# Zio_Qwiic_Hub.net
KiCad netlist of a schematic drawn in EAGLE
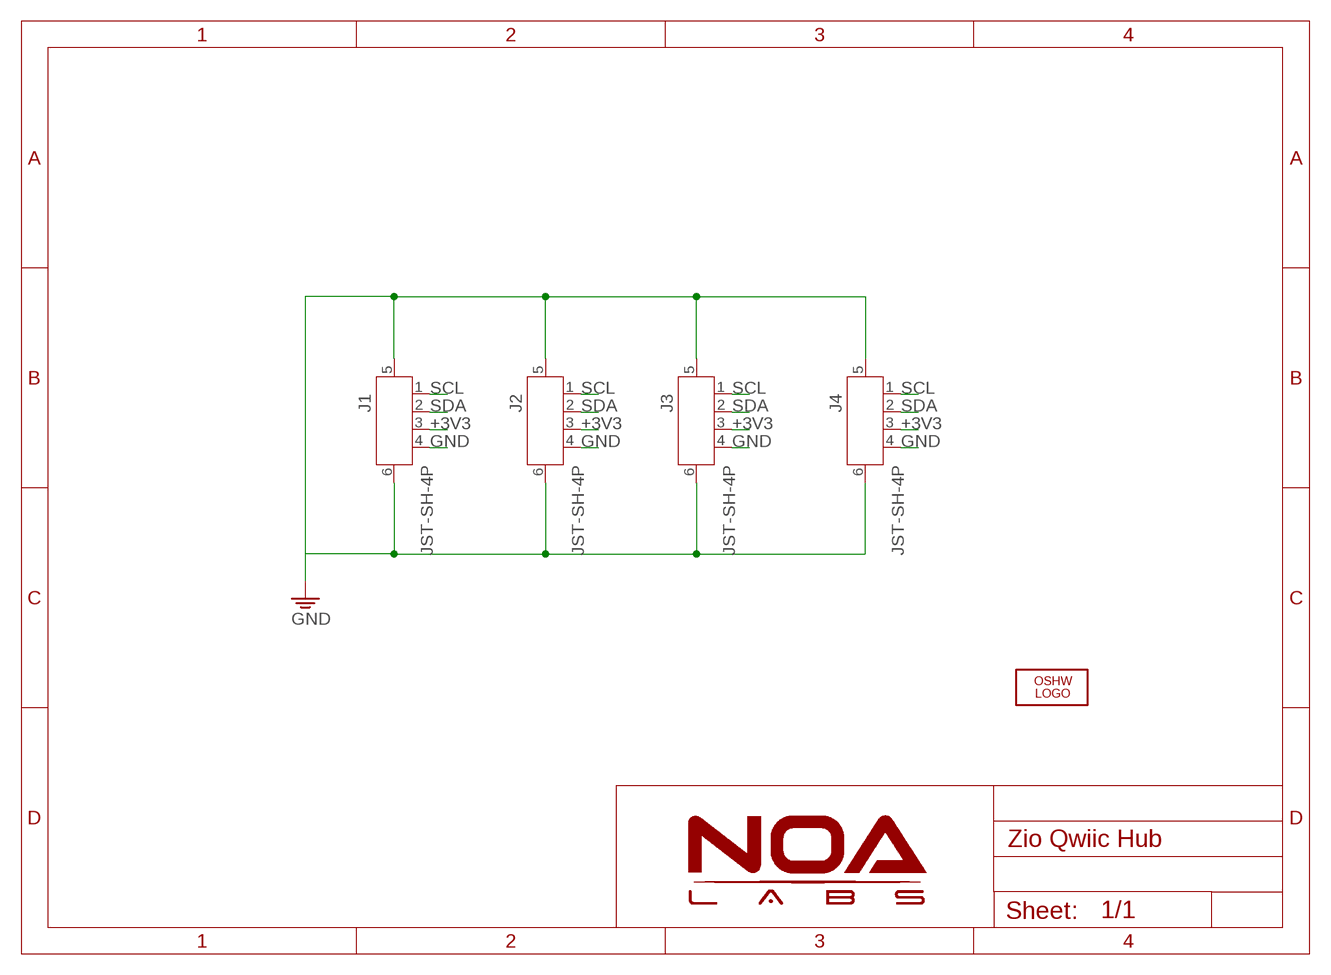
[diagram p0: schematic, sheet 1]

(export (version "E")
  (design (tool "Eeschema 10.0.6"))
  (components
    (comp (ref "J1")
      (value "JST-SH-4P")
      (footprint "eagle-import:JST-SH-4P-90")
      (libsource (lib "eagle-import") (part "JST-SH-4P"))
    )
    (comp (ref "J2")
      (value "JST-SH-4P")
      (footprint "eagle-import:JST-SH-4P-90")
      (libsource (lib "eagle-import") (part "JST-SH-4P"))
    )
    (comp (ref "J3")
      (value "JST-SH-4P")
      (footprint "eagle-import:JST-SH-4P-90")
      (libsource (lib "eagle-import") (part "JST-SH-4P"))
    )
    (comp (ref "J4")
      (value "JST-SH-4P")
      (footprint "eagle-import:JST-SH-4P-90")
      (libsource (lib "eagle-import") (part "JST-SH-4P"))
    )
    (comp (ref "LOGO1")
      (value "LOGO-OSHW-6MILX0070-NT")
      (footprint "eagle-import:OSHW_6X70_NOTEXT")
      (libsource (lib "eagle-import") (part "LOGO-OSHW-6MILX0070-NT"))
    )
  )
  (nets
    (net (code "1") (name "/+3V3") (class "Default")
      (node (ref "J1") (pin "3") (pinfunction "3_3") (pintype "bidirectional"))
      (node (ref "J2") (pin "3") (pinfunction "3_3") (pintype "bidirectional"))
      (node (ref "J3") (pin "3") (pinfunction "3_3") (pintype "bidirectional"))
      (node (ref "J4") (pin "3") (pinfunction "3_3") (pintype "bidirectional"))
    )
    (net (code "2") (name "/SCL") (class "Default")
      (node (ref "J1") (pin "1") (pinfunction "1_1") (pintype "bidirectional"))
      (node (ref "J2") (pin "1") (pinfunction "1_1") (pintype "bidirectional"))
      (node (ref "J3") (pin "1") (pinfunction "1_1") (pintype "bidirectional"))
      (node (ref "J4") (pin "1") (pinfunction "1_1") (pintype "bidirectional"))
    )
    (net (code "3") (name "/SDA") (class "Default")
      (node (ref "J1") (pin "2") (pinfunction "2_2") (pintype "bidirectional"))
      (node (ref "J2") (pin "2") (pinfunction "2_2") (pintype "bidirectional"))
      (node (ref "J3") (pin "2") (pinfunction "2_2") (pintype "bidirectional"))
      (node (ref "J4") (pin "2") (pinfunction "2_2") (pintype "bidirectional"))
    )
    (net (code "4") (name "GND") (class "Default")
      (node (ref "J1") (pin "4") (pinfunction "4_4") (pintype "bidirectional"))
      (node (ref "J1") (pin "5") (pinfunction "5_5") (pintype "bidirectional"))
      (node (ref "J1") (pin "6") (pinfunction "6_6") (pintype "bidirectional"))
      (node (ref "J2") (pin "4") (pinfunction "4_4") (pintype "bidirectional"))
      (node (ref "J2") (pin "5") (pinfunction "5_5") (pintype "bidirectional"))
      (node (ref "J2") (pin "6") (pinfunction "6_6") (pintype "bidirectional"))
      (node (ref "J3") (pin "4") (pinfunction "4_4") (pintype "bidirectional"))
      (node (ref "J3") (pin "5") (pinfunction "5_5") (pintype "bidirectional"))
      (node (ref "J3") (pin "6") (pinfunction "6_6") (pintype "bidirectional"))
      (node (ref "J4") (pin "4") (pinfunction "4_4") (pintype "bidirectional"))
      (node (ref "J4") (pin "5") (pinfunction "5_5") (pintype "bidirectional"))
      (node (ref "J4") (pin "6") (pinfunction "6_6") (pintype "bidirectional"))
    )
  )
)
